# TTAmp_Mechanical.net
KiCad netlist of a schematic drawn in Altium Designer
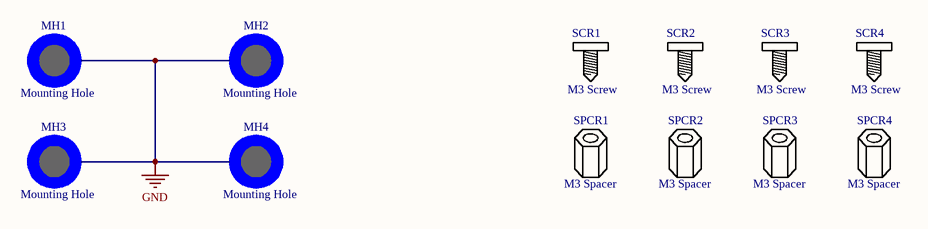
[diagram p0: TTAmp_Mechanical.SchDoc]

(export (version "E")
  (design (tool "Eeschema 10.0.6"))
  (components
    (comp (ref "MH1")
      (value "Mounting Hole")
      (footprint "MH-M3_Copper")
      (description "M3 mounting hole")
      (libsource (lib "PCB") (part "MH"))
    )
    (comp (ref "MH2")
      (value "Mounting Hole")
      (footprint "MH-M3_Copper")
      (description "M3 mounting hole")
      (libsource (lib "PCB") (part "MH"))
    )
    (comp (ref "MH3")
      (value "Mounting Hole")
      (footprint "MH-M3_Copper")
      (description "M3 mounting hole")
      (libsource (lib "PCB") (part "MH"))
    )
    (comp (ref "MH4")
      (value "Mounting Hole")
      (footprint "MH-M3_Copper")
      (description "M3 mounting hole")
      (libsource (lib "PCB") (part "MH"))
    )
    (comp (ref "SCR1") (value "M3 Screw") (libsource (lib "Mechanical") (part "SCREW")))
    (comp (ref "SCR2") (value "M3 Screw") (libsource (lib "Mechanical") (part "SCREW")))
    (comp (ref "SCR3") (value "M3 Screw") (libsource (lib "Mechanical") (part "SCREW")))
    (comp (ref "SCR4") (value "M3 Screw") (libsource (lib "Mechanical") (part "SCREW")))
    (comp (ref "SPCR1") (value "M3 Spacer") (libsource (lib "Mechanical") (part "SPCR")))
    (comp (ref "SPCR2") (value "M3 Spacer") (libsource (lib "Mechanical") (part "SPCR")))
    (comp (ref "SPCR3") (value "M3 Spacer") (libsource (lib "Mechanical") (part "SPCR")))
    (comp (ref "SPCR4") (value "M3 Spacer") (libsource (lib "Mechanical") (part "SPCR")))
  )
  (nets
    (net (code "1") (name "GND") (class "Default")
      (node (ref "MH1") (pin "MH") (pinfunction "MH_MH") (pintype "passive"))
      (node (ref "MH2") (pin "MH") (pinfunction "MH_MH") (pintype "passive"))
      (node (ref "MH3") (pin "MH") (pinfunction "MH_MH") (pintype "passive"))
      (node (ref "MH4") (pin "MH") (pinfunction "MH_MH") (pintype "passive"))
    )
  )
)
